# sound.net
KiCad netlist of a schematic drawn in EAGLE
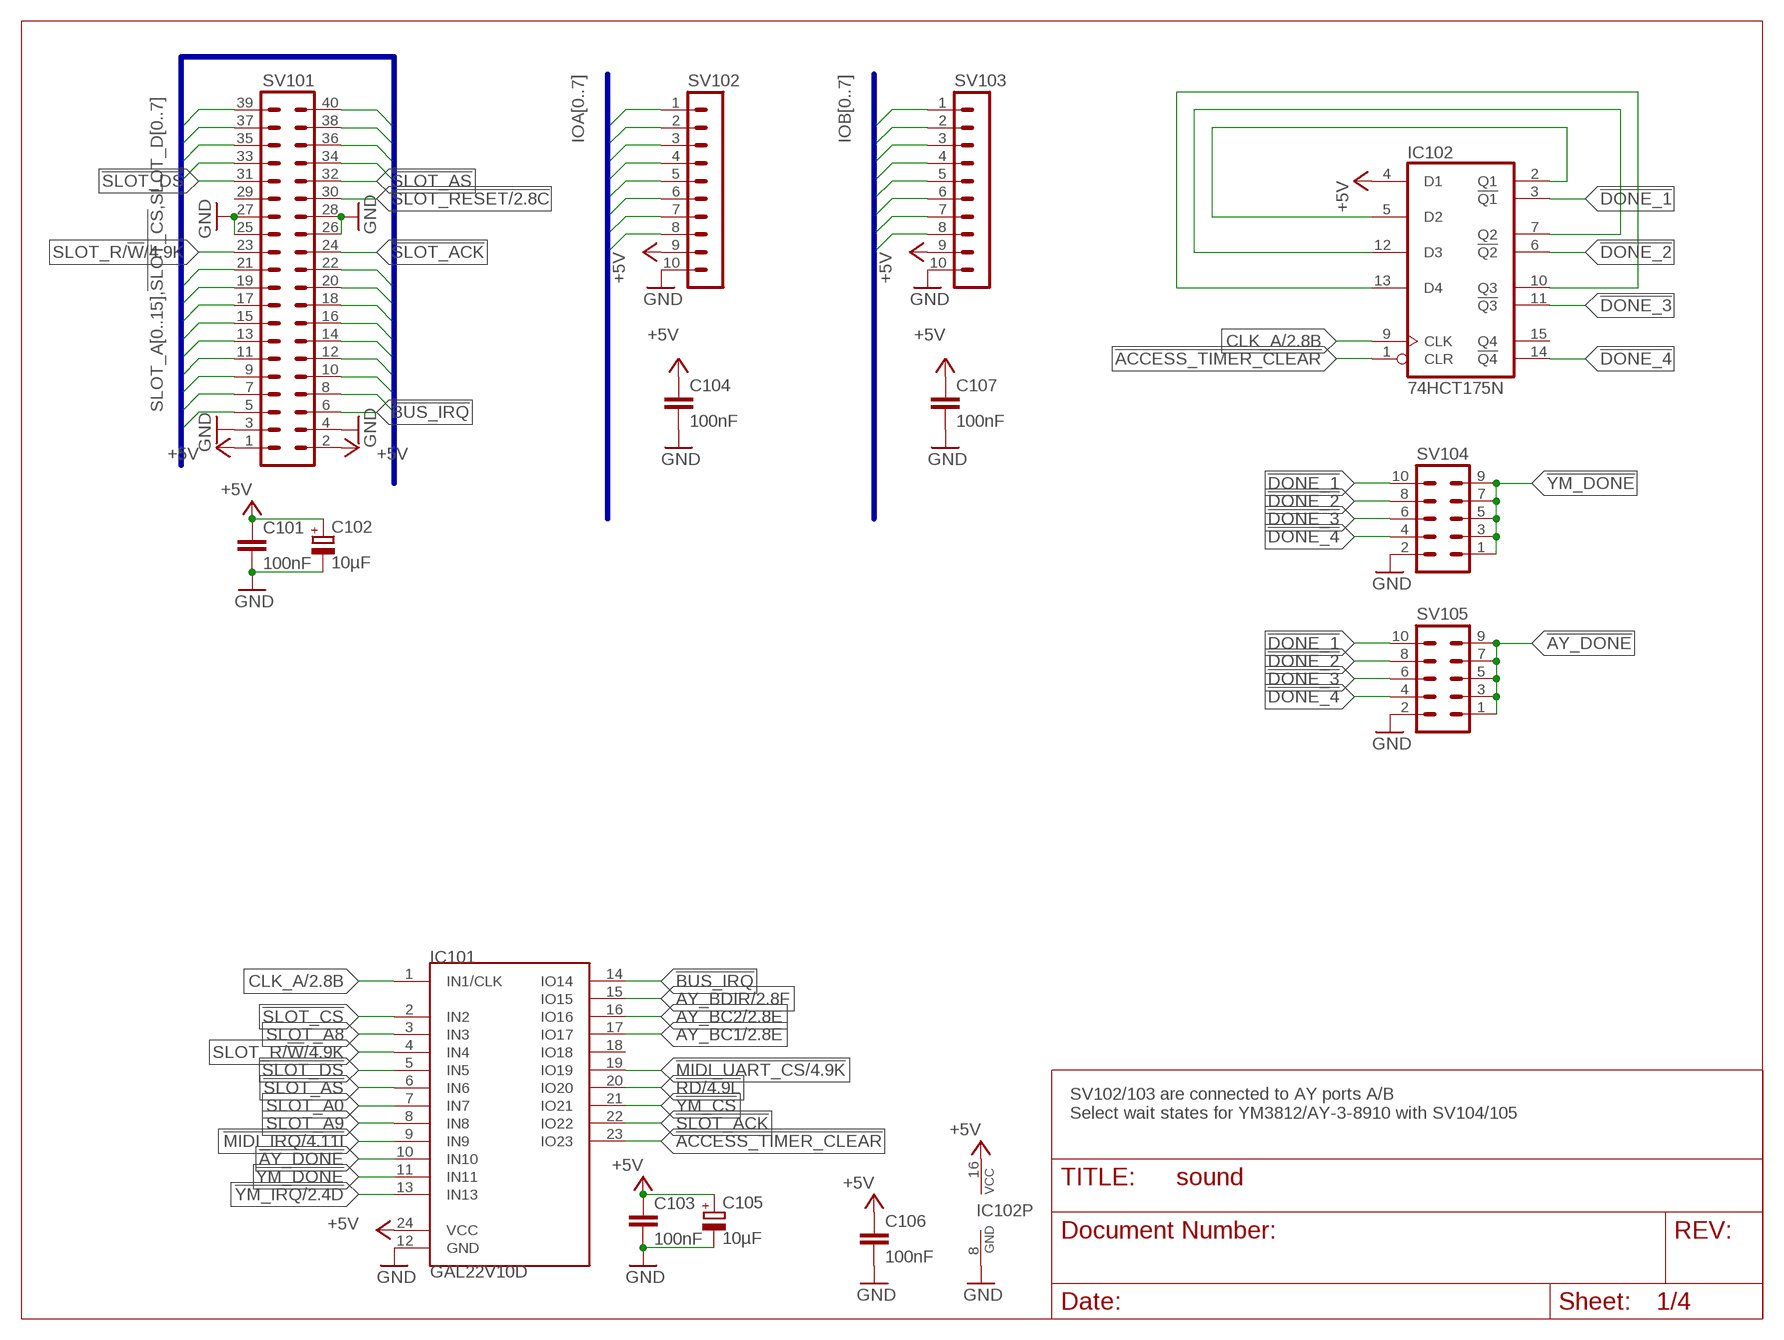
[diagram p0: schematic, sheet 1]
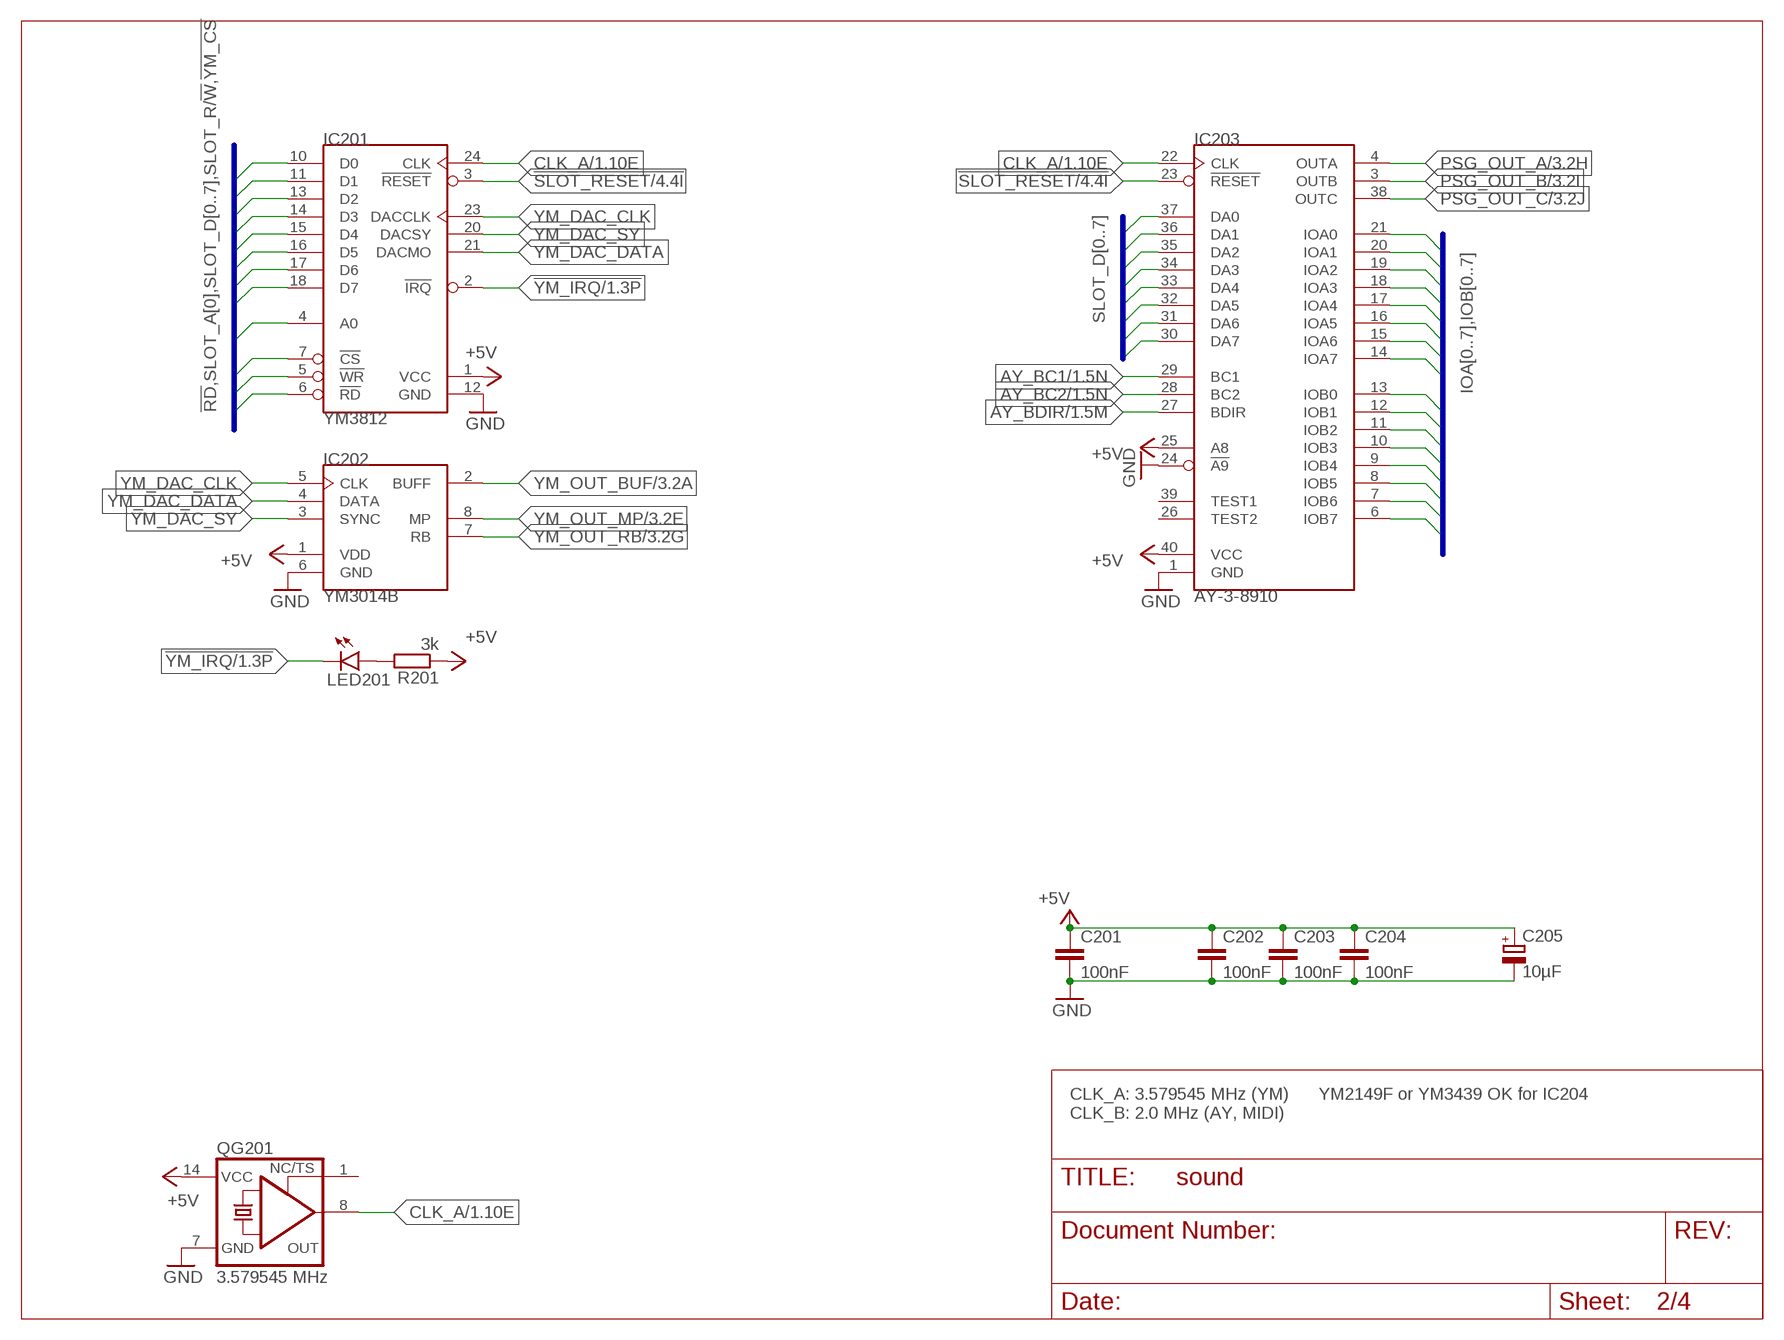
[diagram p1: schematic, sheet 2]
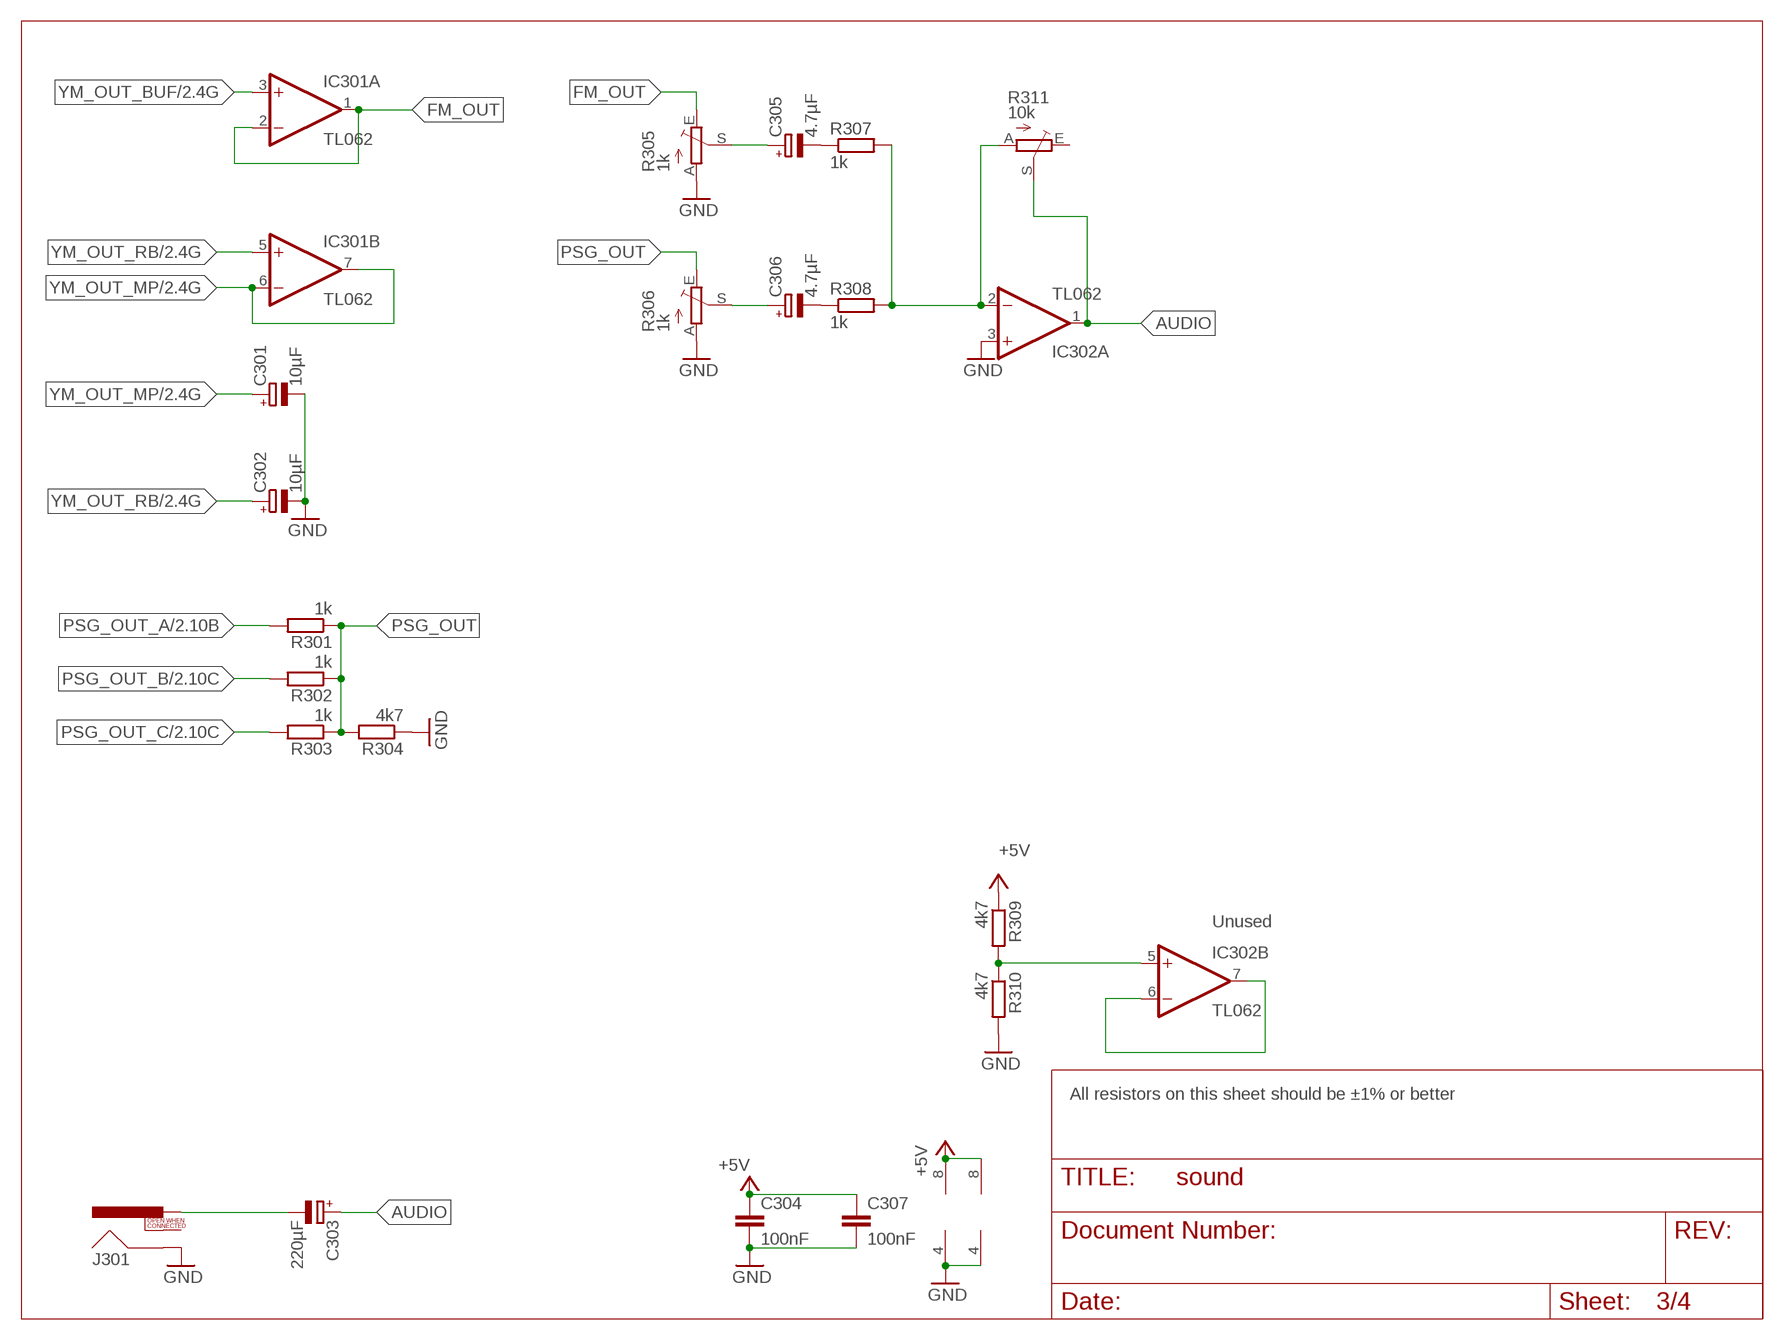
[diagram p2: schematic, sheet 3]
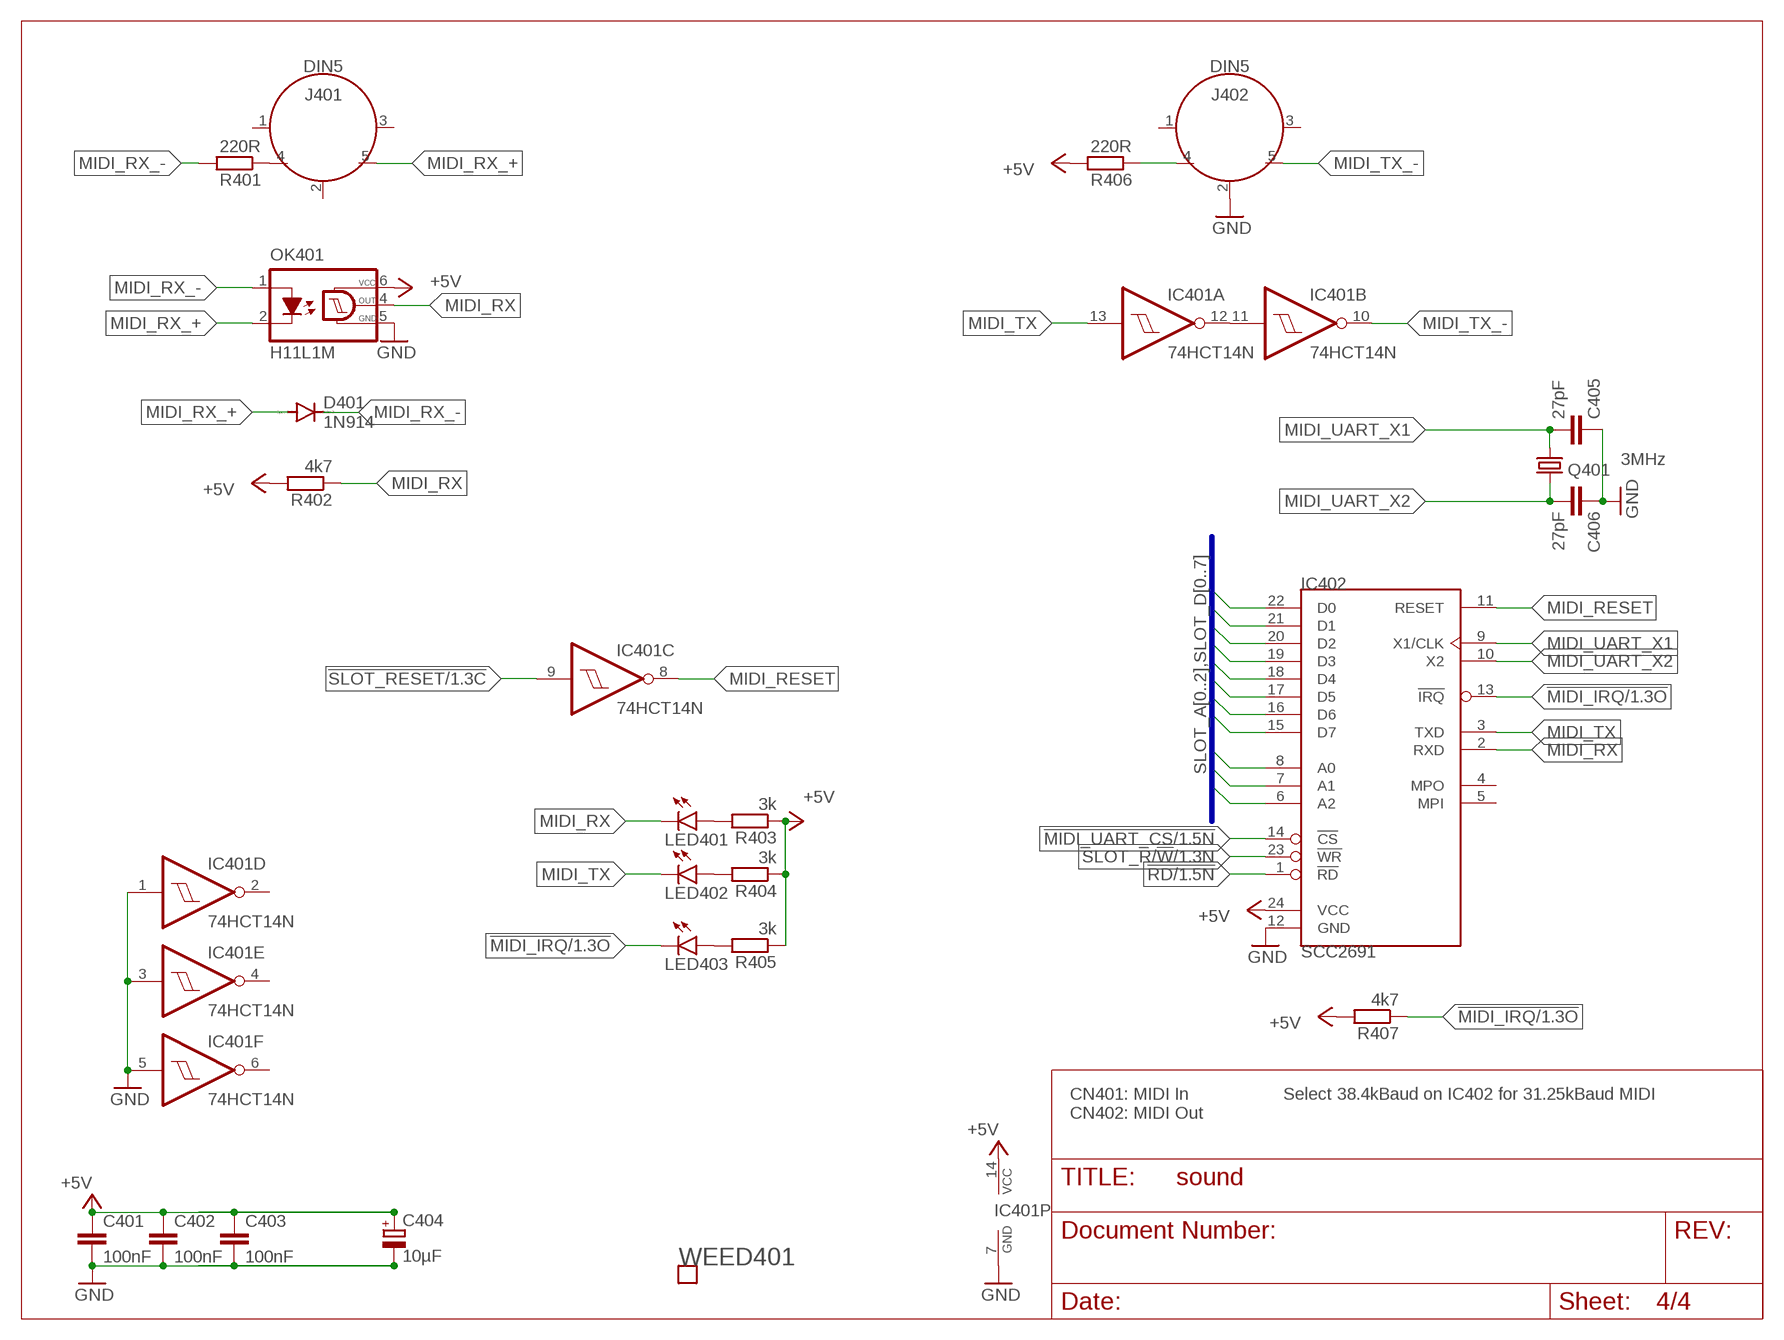
[diagram p3: schematic, sheet 4]

(export (version "E")
  (design (tool "Eeschema 10.0.6"))
  (components
    (comp (ref "C401")
      (value "100nF")
      (footprint "eagle-import:C0805")
      (libsource (lib "eagle-import") (part "C-EUC0805"))
    )
    (comp (ref "C402")
      (value "100nF")
      (footprint "eagle-import:C0805")
      (libsource (lib "eagle-import") (part "C-EUC0805"))
    )
    (comp (ref "C403")
      (value "100nF")
      (footprint "eagle-import:C0805")
      (libsource (lib "eagle-import") (part "C-EUC0805"))
    )
    (comp (ref "C404")
      (value "10µF")
      (footprint "eagle-import:SMC_B")
      (libsource (lib "eagle-import") (part "CPOL-EUSMCB"))
    )
    (comp (ref "C405")
      (value "27pF")
      (footprint "eagle-import:C0805")
      (libsource (lib "eagle-import") (part "C-EUC0805"))
    )
    (comp (ref "C406")
      (value "27pF")
      (footprint "eagle-import:C0805")
      (libsource (lib "eagle-import") (part "C-EUC0805"))
    )
    (comp (ref "D401")
      (value "1N914")
      (footprint "eagle-import:DO35-10")
      (libsource (lib "eagle-import") (part "1N4148DO35-10"))
    )
    (comp (ref "IC401")
      (value "74HCT14N")
      (footprint "eagle-import:DIL14")
      (fields (field (name "MOUSER") "595-SN74HCT14N") (field (name "MOUSER_SOCKET") "575-1104731441001000"))
      (libsource (lib "eagle-import") (part "7414NHCT"))
    )
    (comp (ref "IC402")
      (value "SCC2691")
      (footprint "eagle-import:DIL24S")
      (libsource (lib "eagle-import") (part "SCC2691"))
    )
    (comp (ref "J401")
      (value "DIN5")
      (footprint "eagle-import:DIN5-RA-PTH")
      (libsource (lib "eagle-import") (part "DIN5"))
    )
    (comp (ref "J402")
      (value "DIN5")
      (footprint "eagle-import:DIN5-RA-PTH")
      (libsource (lib "eagle-import") (part "DIN5"))
    )
    (comp (ref "LED401")
      (value "LEDCHIPLED_1206")
      (footprint "eagle-import:CHIPLED_1206")
      (libsource (lib "eagle-import") (part "LEDCHIPLED_1206"))
    )
    (comp (ref "LED402")
      (value "LEDCHIPLED_1206")
      (footprint "eagle-import:CHIPLED_1206")
      (libsource (lib "eagle-import") (part "LEDCHIPLED_1206"))
    )
    (comp (ref "LED403")
      (value "LEDCHIPLED_1206")
      (footprint "eagle-import:CHIPLED_1206")
      (libsource (lib "eagle-import") (part "LEDCHIPLED_1206"))
    )
    (comp (ref "OK401")
      (value "H11L1M")
      (footprint "eagle-import:DIL06")
      (fields (field (name "MF") "FAIRCHILD SEMICONDUCTOR") (field (name "MPN") "H11L1-M"))
      (libsource (lib "eagle-import") (part "H11LM1"))
    )
    (comp (ref "Q401")
      (value "3MHz")
      (footprint "eagle-import:HC49_S")
      (libsource (lib "eagle-import") (part "CRYSTALHC49S"))
    )
    (comp (ref "R401")
      (value "220R")
      (footprint "eagle-import:R2012")
      (libsource (lib "eagle-import") (part "R-EU_R2012"))
    )
    (comp (ref "R402")
      (value "4k7")
      (footprint "eagle-import:R2012")
      (libsource (lib "eagle-import") (part "R-EU_R2012"))
    )
    (comp (ref "R403")
      (value "3k")
      (footprint "eagle-import:R2012")
      (libsource (lib "eagle-import") (part "R-EU_R2012"))
    )
    (comp (ref "R404")
      (value "3k")
      (footprint "eagle-import:R2012")
      (libsource (lib "eagle-import") (part "R-EU_R2012"))
    )
    (comp (ref "R405")
      (value "3k")
      (footprint "eagle-import:R2012")
      (libsource (lib "eagle-import") (part "R-EU_R2012"))
    )
    (comp (ref "R406")
      (value "220R")
      (footprint "eagle-import:R2012")
      (libsource (lib "eagle-import") (part "R-EU_R2012"))
    )
    (comp (ref "R407")
      (value "4k7")
      (footprint "eagle-import:R2012")
      (libsource (lib "eagle-import") (part "R-EU_R2012"))
    )
    (comp (ref "WEED401")
      (value "WEED")
      (footprint "eagle-import:DOINK")
      (libsource (lib "eagle-import") (part "WEED"))
    )
    (comp (ref "C301")
      (value "10µF")
      (footprint "eagle-import:E2-5")
      (libsource (lib "eagle-import") (part "CPOL-EUE2-5"))
    )
    (comp (ref "C302")
      (value "10µF")
      (footprint "eagle-import:E2-5")
      (libsource (lib "eagle-import") (part "CPOL-EUE2-5"))
    )
    (comp (ref "C303")
      (value "220µF")
      (footprint "eagle-import:E2,5-6")
      (libsource (lib "eagle-import") (part "CPOL-EUE2.5-6"))
    )
    (comp (ref "C304")
      (value "100nF")
      (footprint "eagle-import:C0805")
      (libsource (lib "eagle-import") (part "C-EUC0805"))
    )
    (comp (ref "C305")
      (value "4.7µF")
      (footprint "eagle-import:E2-5")
      (libsource (lib "eagle-import") (part "CPOL-EUE2-5"))
    )
    (comp (ref "C306")
      (value "4.7µF")
      (footprint "eagle-import:E2-5")
      (libsource (lib "eagle-import") (part "CPOL-EUE2-5"))
    )
    (comp (ref "C307")
      (value "100nF")
      (footprint "eagle-import:C0805")
      (libsource (lib "eagle-import") (part "C-EUC0805"))
    )
    (comp (ref "IC301")
      (value "TL062")
      (footprint "eagle-import:DIL08")
      (fields
        (field (name "MOUSER") "595-TL062CP")
        (field (name "MOUSER_SOCKET") "575-1104730841001000")
        (field (name "SPICEPREFIX") "J")
      )
      (libsource (lib "eagle-import") (part "TL062P"))
    )
    (comp (ref "IC302")
      (value "TL062")
      (footprint "eagle-import:DIL08")
      (fields
        (field (name "MOUSER") "595-TL062CP")
        (field (name "MOUSER_SOCKET") "575-1104730841001000")
        (field (name "SPICEPREFIX") "J")
      )
      (libsource (lib "eagle-import") (part "TL062P"))
    )
    (comp (ref "J301")
      (value "RCALOCK")
      (footprint "eagle-import:RCA_LOCK")
      (libsource (lib "eagle-import") (part "RCALOCK"))
    )
    (comp (ref "R301")
      (value "1k")
      (footprint "eagle-import:R2012")
      (libsource (lib "eagle-import") (part "R-EU_R2012"))
    )
    (comp (ref "R302")
      (value "1k")
      (footprint "eagle-import:R2012")
      (libsource (lib "eagle-import") (part "R-EU_R2012"))
    )
    (comp (ref "R303")
      (value "1k")
      (footprint "eagle-import:R2012")
      (libsource (lib "eagle-import") (part "R-EU_R2012"))
    )
    (comp (ref "R304")
      (value "4k7")
      (footprint "eagle-import:R2012")
      (libsource (lib "eagle-import") (part "R-EU_R2012"))
    )
    (comp (ref "R305")
      (value "1k")
      (footprint "eagle-import:PT-10S")
      (fields (field (name "SPICEPREFIX") "J"))
      (libsource (lib "eagle-import") (part "TRIM_EU-PT10S"))
    )
    (comp (ref "R306")
      (value "1k")
      (footprint "eagle-import:PT-10S")
      (fields (field (name "SPICEPREFIX") "J"))
      (libsource (lib "eagle-import") (part "TRIM_EU-PT10S"))
    )
    (comp (ref "R307")
      (value "1k")
      (footprint "eagle-import:R2012")
      (libsource (lib "eagle-import") (part "R-EU_R2012"))
    )
    (comp (ref "R308")
      (value "1k")
      (footprint "eagle-import:R2012")
      (libsource (lib "eagle-import") (part "R-EU_R2012"))
    )
    (comp (ref "R309")
      (value "4k7")
      (footprint "eagle-import:R2012")
      (libsource (lib "eagle-import") (part "R-EU_R2012"))
    )
    (comp (ref "R310")
      (value "4k7")
      (footprint "eagle-import:R2012")
      (libsource (lib "eagle-import") (part "R-EU_R2012"))
    )
    (comp (ref "R311")
      (value "10k")
      (footprint "eagle-import:PT-10S")
      (fields (field (name "SPICEPREFIX") "J"))
      (libsource (lib "eagle-import") (part "TRIM_EU-PT10S"))
    )
    (comp (ref "C101")
      (value "100nF")
      (footprint "eagle-import:C0805")
      (libsource (lib "eagle-import") (part "C-EUC0805"))
    )
    (comp (ref "C102")
      (value "10µF")
      (footprint "eagle-import:SMC_B")
      (libsource (lib "eagle-import") (part "CPOL-EUSMCB"))
    )
    (comp (ref "C103")
      (value "100nF")
      (footprint "eagle-import:C0805")
      (libsource (lib "eagle-import") (part "C-EUC0805"))
    )
    (comp (ref "C104")
      (value "100nF")
      (footprint "eagle-import:C0805")
      (libsource (lib "eagle-import") (part "C-EUC0805"))
    )
    (comp (ref "C105")
      (value "10µF")
      (footprint "eagle-import:SMC_B")
      (libsource (lib "eagle-import") (part "CPOL-EUSMCB"))
    )
    (comp (ref "C106")
      (value "100nF")
      (footprint "eagle-import:C0805")
      (libsource (lib "eagle-import") (part "C-EUC0805"))
    )
    (comp (ref "C107")
      (value "100nF")
      (footprint "eagle-import:C0805")
      (libsource (lib "eagle-import") (part "C-EUC0805"))
    )
    (comp (ref "IC101")
      (value "GAL22V10D")
      (footprint "eagle-import:DIL24S")
      (libsource (lib "eagle-import") (part "GAL22V10DIP24"))
    )
    (comp (ref "IC102")
      (value "74HCT175N")
      (footprint "eagle-import:DIL16")
      (fields (field (name "MOUSER") "595-CD74HCT175E") (field (name "MOUSER_SOCKET") "575-1104731641001000"))
      (libsource (lib "eagle-import") (part "74175NHCT"))
    )
    (comp (ref "SV101")
      (value "MA20-2W")
      (footprint "eagle-import:MA20-2W")
      (libsource (lib "eagle-import") (part "MA20-2W"))
    )
    (comp (ref "SV102")
      (value "MA10-1")
      (footprint "eagle-import:MA10-1")
      (libsource (lib "eagle-import") (part "MA10-1"))
    )
    (comp (ref "SV103")
      (value "MA10-1")
      (footprint "eagle-import:MA10-1")
      (libsource (lib "eagle-import") (part "MA10-1"))
    )
    (comp (ref "SV104")
      (value "MA05-2")
      (footprint "eagle-import:MA05-2")
      (libsource (lib "eagle-import") (part "MA05-2"))
    )
    (comp (ref "SV105")
      (value "MA05-2")
      (footprint "eagle-import:MA05-2")
      (libsource (lib "eagle-import") (part "MA05-2"))
    )
    (comp (ref "C201")
      (value "100nF")
      (footprint "eagle-import:C0805")
      (libsource (lib "eagle-import") (part "C-EUC0805"))
    )
    (comp (ref "C202")
      (value "100nF")
      (footprint "eagle-import:C0805")
      (libsource (lib "eagle-import") (part "C-EUC0805"))
    )
    (comp (ref "C203")
      (value "100nF")
      (footprint "eagle-import:C0805")
      (libsource (lib "eagle-import") (part "C-EUC0805"))
    )
    (comp (ref "C204")
      (value "100nF")
      (footprint "eagle-import:C0805")
      (libsource (lib "eagle-import") (part "C-EUC0805"))
    )
    (comp (ref "C205")
      (value "10µF")
      (footprint "eagle-import:SMC_B")
      (libsource (lib "eagle-import") (part "CPOL-EUSMCB"))
    )
    (comp (ref "IC201")
      (value "YM3812")
      (footprint "eagle-import:DIL24")
      (libsource (lib "eagle-import") (part "YM3812DIL24"))
    )
    (comp (ref "IC202")
      (value "YM3014B")
      (footprint "eagle-import:DIL8")
      (libsource (lib "eagle-import") (part "YM3014BDIL8"))
    )
    (comp (ref "IC203")
      (value "AY-3-8910")
      (footprint "eagle-import:DIL40")
      (libsource (lib "eagle-import") (part "AY-3-8910"))
    )
    (comp (ref "LED201")
      (value "LEDCHIPLED_1206")
      (footprint "eagle-import:CHIPLED_1206")
      (libsource (lib "eagle-import") (part "LEDCHIPLED_1206"))
    )
    (comp (ref "QG201")
      (value "3.579545 MHz")
      (footprint "eagle-import:DIL14S")
      (libsource (lib "eagle-import") (part "XO-14"))
    )
    (comp (ref "R201")
      (value "3k")
      (footprint "eagle-import:R2012")
      (libsource (lib "eagle-import") (part "R-EU_R2012"))
    )
  )
  (nets
    (net (code "2") (name "+5V") (class "Default")
      (node (ref "C101") (pin "1") (pinfunction "1_1") (pintype "passive"))
      (node (ref "C102") (pin "+") (pinfunction "+_+") (pintype "passive"))
      (node (ref "C103") (pin "1") (pinfunction "1_1") (pintype "passive"))
      (node (ref "C104") (pin "1") (pinfunction "1_1") (pintype "passive"))
      (node (ref "C105") (pin "+") (pinfunction "+_+") (pintype "passive"))
      (node (ref "C106") (pin "1") (pinfunction "1_1") (pintype "passive"))
      (node (ref "C107") (pin "1") (pinfunction "1_1") (pintype "passive"))
      (node (ref "C201") (pin "1") (pinfunction "1_1") (pintype "passive"))
      (node (ref "C202") (pin "1") (pinfunction "1_1") (pintype "passive"))
      (node (ref "C203") (pin "1") (pinfunction "1_1") (pintype "passive"))
      (node (ref "C204") (pin "1") (pinfunction "1_1") (pintype "passive"))
      (node (ref "C205") (pin "+") (pinfunction "+_+") (pintype "passive"))
      (node (ref "C304") (pin "1") (pinfunction "1_1") (pintype "passive"))
      (node (ref "C307") (pin "1") (pinfunction "1_1") (pintype "passive"))
      (node (ref "C401") (pin "1") (pinfunction "1_1") (pintype "passive"))
      (node (ref "C402") (pin "1") (pinfunction "1_1") (pintype "passive"))
      (node (ref "C403") (pin "1") (pinfunction "1_1") (pintype "passive"))
      (node (ref "C404") (pin "+") (pinfunction "+_+") (pintype "passive"))
      (node (ref "IC101") (pin "24") (pinfunction "VCC_24") (pintype "power_in"))
      (node (ref "IC102") (pin "16") (pinfunction "VCC_16") (pintype "power_in"))
      (node (ref "IC102") (pin "4") (pinfunction "D1_4") (pintype "input"))
      (node (ref "IC201") (pin "1") (pinfunction "VCC_1") (pintype "power_in"))
      (node (ref "IC202") (pin "1") (pinfunction "VDD_1") (pintype "power_in"))
      (node (ref "IC203") (pin "25") (pinfunction "A8_25") (pintype "input"))
      (node (ref "IC203") (pin "40") (pinfunction "VCC_40") (pintype "power_in"))
      (node (ref "IC301") (pin "8") (pinfunction "V+_8") (pintype "power_in"))
      (node (ref "IC302") (pin "8") (pinfunction "V+_8") (pintype "power_in"))
      (node (ref "IC401") (pin "14") (pinfunction "VCC_14") (pintype "power_in"))
      (node (ref "IC402") (pin "24") (pinfunction "VCC_24") (pintype "power_in"))
      (node (ref "OK401") (pin "6") (pinfunction "VCC_6") (pintype "power_in"))
      (node (ref "QG201") (pin "14") (pinfunction "VCC_14") (pintype "power_in"))
      (node (ref "R201") (pin "1") (pinfunction "1_1") (pintype "passive"))
      (node (ref "R309") (pin "1") (pinfunction "1_1") (pintype "passive"))
      (node (ref "R402") (pin "2") (pinfunction "2_2") (pintype "passive"))
      (node (ref "R403") (pin "1") (pinfunction "1_1") (pintype "passive"))
      (node (ref "R404") (pin "1") (pinfunction "1_1") (pintype "passive"))
      (node (ref "R405") (pin "1") (pinfunction "1_1") (pintype "passive"))
      (node (ref "R406") (pin "2") (pinfunction "2_2") (pintype "passive"))
      (node (ref "R407") (pin "2") (pinfunction "2_2") (pintype "passive"))
      (node (ref "SV101") (pin "1") (pinfunction "1_1") (pintype "passive"))
      (node (ref "SV101") (pin "2") (pinfunction "2_2") (pintype "passive"))
      (node (ref "SV102") (pin "9") (pinfunction "9_9") (pintype "passive"))
      (node (ref "SV103") (pin "9") (pinfunction "9_9") (pintype "passive"))
    )
    (net (code "10") (name "AUDIO") (class "Default")
      (node (ref "C303") (pin "+") (pinfunction "+_+") (pintype "passive"))
      (node (ref "IC302") (pin "1") (pinfunction "OUT_1") (pintype "output"))
      (node (ref "R311") (pin "S") (pinfunction "S_S") (pintype "passive"))
    )
    (net (code "11") (name "AY_BC1") (class "Default")
      (node (ref "IC101") (pin "17") (pinfunction "IO17_17") (pintype "bidirectional"))
      (node (ref "IC203") (pin "29") (pinfunction "BC1_29") (pintype "input"))
    )
    (net (code "12") (name "AY_BC2") (class "Default")
      (node (ref "IC101") (pin "16") (pinfunction "IO16_16") (pintype "bidirectional"))
      (node (ref "IC203") (pin "28") (pinfunction "BC2_28") (pintype "input"))
    )
    (net (code "13") (name "AY_BDIR") (class "Default")
      (node (ref "IC101") (pin "15") (pinfunction "IO15_15") (pintype "bidirectional"))
      (node (ref "IC203") (pin "27") (pinfunction "BDIR_27") (pintype "input"))
    )
    (net (code "14") (name "CLK_A") (class "Default")
      (node (ref "IC101") (pin "1") (pinfunction "IN1/CLK_1") (pintype "input"))
      (node (ref "IC102") (pin "9") (pinfunction "CLK_9") (pintype "input"))
      (node (ref "IC201") (pin "24") (pinfunction "CLK_24") (pintype "input"))
      (node (ref "IC203") (pin "22") (pinfunction "CLK_22") (pintype "input"))
      (node (ref "QG201") (pin "8") (pinfunction "OUT_8") (pintype "output"))
    )
    (net (code "15") (name "FM_OUT") (class "Default")
      (node (ref "IC301") (pin "1") (pinfunction "OUT_1") (pintype "output"))
      (node (ref "IC301") (pin "2") (pinfunction "-IN_2") (pintype "input"))
      (node (ref "R305") (pin "E") (pinfunction "E_E") (pintype "passive"))
    )
    (net (code "16") (name "GND") (class "Default")
      (node (ref "C101") (pin "2") (pinfunction "2_2") (pintype "passive"))
      (node (ref "C102") (pin "-") (pinfunction "-_-") (pintype "passive"))
      (node (ref "C103") (pin "2") (pinfunction "2_2") (pintype "passive"))
      (node (ref "C104") (pin "2") (pinfunction "2_2") (pintype "passive"))
      (node (ref "C105") (pin "-") (pinfunction "-_-") (pintype "passive"))
      (node (ref "C106") (pin "2") (pinfunction "2_2") (pintype "passive"))
      (node (ref "C107") (pin "2") (pinfunction "2_2") (pintype "passive"))
      (node (ref "C201") (pin "2") (pinfunction "2_2") (pintype "passive"))
      (node (ref "C202") (pin "2") (pinfunction "2_2") (pintype "passive"))
      (node (ref "C203") (pin "2") (pinfunction "2_2") (pintype "passive"))
      (node (ref "C204") (pin "2") (pinfunction "2_2") (pintype "passive"))
      (node (ref "C205") (pin "-") (pinfunction "-_-") (pintype "passive"))
      (node (ref "C301") (pin "-") (pinfunction "-_-") (pintype "passive"))
      (node (ref "C302") (pin "-") (pinfunction "-_-") (pintype "passive"))
      (node (ref "C304") (pin "2") (pinfunction "2_2") (pintype "passive"))
      (node (ref "C307") (pin "2") (pinfunction "2_2") (pintype "passive"))
      (node (ref "C401") (pin "2") (pinfunction "2_2") (pintype "passive"))
      (node (ref "C402") (pin "2") (pinfunction "2_2") (pintype "passive"))
      (node (ref "C403") (pin "2") (pinfunction "2_2") (pintype "passive"))
      (node (ref "C404") (pin "-") (pinfunction "-_-") (pintype "passive"))
      (node (ref "C405") (pin "1") (pinfunction "1_1") (pintype "passive"))
      (node (ref "C406") (pin "1") (pinfunction "1_1") (pintype "passive"))
      (node (ref "IC101") (pin "12") (pinfunction "GND_12") (pintype "power_in"))
      (node (ref "IC102") (pin "8") (pinfunction "GND_8") (pintype "power_in"))
      (node (ref "IC201") (pin "12") (pinfunction "GND_12") (pintype "power_in"))
      (node (ref "IC202") (pin "6") (pinfunction "GND_6") (pintype "power_in"))
      (node (ref "IC203") (pin "1") (pinfunction "GND_1") (pintype "power_in"))
      (node (ref "IC203") (pin "24") (pinfunction "~{A9}_24") (pintype "input"))
      (node (ref "IC301") (pin "4") (pinfunction "V-_4") (pintype "power_in"))
      (node (ref "IC302") (pin "3") (pinfunction "+IN_3") (pintype "input"))
      (node (ref "IC302") (pin "4") (pinfunction "V-_4") (pintype "power_in"))
      (node (ref "IC401") (pin "1") (pinfunction "I_1") (pintype "input"))
      (node (ref "IC401") (pin "3") (pinfunction "I_3") (pintype "input"))
      (node (ref "IC401") (pin "5") (pinfunction "I_5") (pintype "input"))
      (node (ref "IC401") (pin "7") (pinfunction "GND_7") (pintype "power_in"))
      (node (ref "IC402") (pin "12") (pinfunction "GND_12") (pintype "power_in"))
      (node (ref "J301") (pin "SHELL") (pinfunction "SHELL_SHELL") (pintype "bidirectional"))
      (node (ref "J402") (pin "2") (pinfunction "2_2") (pintype "bidirectional"))
      (node (ref "OK401") (pin "5") (pinfunction "GND_5") (pintype "power_in"))
      (node (ref "QG201") (pin "7") (pinfunction "GND_7") (pintype "power_in"))
      (node (ref "R304") (pin "1") (pinfunction "1_1") (pintype "passive"))
      (node (ref "R305") (pin "A") (pinfunction "A_A") (pintype "passive"))
      (node (ref "R306") (pin "A") (pinfunction "A_A") (pintype "passive"))
      (node (ref "R310") (pin "2") (pinfunction "2_2") (pintype "passive"))
      (node (ref "SV101") (pin "25") (pinfunction "25_25") (pintype "passive"))
      (node (ref "SV101") (pin "26") (pinfunction "26_26") (pintype "passive"))
      (node (ref "SV101") (pin "27") (pinfunction "27_27") (pintype "passive"))
      (node (ref "SV101") (pin "28") (pinfunction "28_28") (pintype "passive"))
      (node (ref "SV101") (pin "3") (pinfunction "3_3") (pintype "passive"))
      (node (ref "SV101") (pin "4") (pinfunction "4_4") (pintype "passive"))
      (node (ref "SV102") (pin "10") (pinfunction "10_10") (pintype "passive"))
      (node (ref "SV103") (pin "10") (pinfunction "10_10") (pintype "passive"))
      (node (ref "SV104") (pin "2") (pinfunction "2_2") (pintype "passive"))
      (node (ref "SV105") (pin "2") (pinfunction "2_2") (pintype "passive"))
    )
    (net (code "17") (name "IOA0") (class "Default")
      (node (ref "IC203") (pin "21") (pinfunction "IOA0_21") (pintype "bidirectional"))
      (node (ref "SV102") (pin "1") (pinfunction "1_1") (pintype "passive"))
    )
    (net (code "18") (name "IOA1") (class "Default")
      (node (ref "IC203") (pin "20") (pinfunction "IOA1_20") (pintype "bidirectional"))
      (node (ref "SV102") (pin "2") (pinfunction "2_2") (pintype "passive"))
    )
    (net (code "19") (name "IOA2") (class "Default")
      (node (ref "IC203") (pin "19") (pinfunction "IOA2_19") (pintype "bidirectional"))
      (node (ref "SV102") (pin "3") (pinfunction "3_3") (pintype "passive"))
    )
    (net (code "20") (name "IOA3") (class "Default")
      (node (ref "IC203") (pin "18") (pinfunction "IOA3_18") (pintype "bidirectional"))
      (node (ref "SV102") (pin "4") (pinfunction "4_4") (pintype "passive"))
    )
    (net (code "21") (name "IOA4") (class "Default")
      (node (ref "IC203") (pin "17") (pinfunction "IOA4_17") (pintype "bidirectional"))
      (node (ref "SV102") (pin "5") (pinfunction "5_5") (pintype "passive"))
    )
    (net (code "22") (name "IOA5") (class "Default")
      (node (ref "IC203") (pin "16") (pinfunction "IOA5_16") (pintype "bidirectional"))
      (node (ref "SV102") (pin "6") (pinfunction "6_6") (pintype "passive"))
    )
    (net (code "23") (name "IOA6") (class "Default")
      (node (ref "IC203") (pin "15") (pinfunction "IOA6_15") (pintype "bidirectional"))
      (node (ref "SV102") (pin "7") (pinfunction "7_7") (pintype "passive"))
    )
    (net (code "24") (name "IOA7") (class "Default")
      (node (ref "IC203") (pin "14") (pinfunction "IOA7_14") (pintype "bidirectional"))
      (node (ref "SV102") (pin "8") (pinfunction "8_8") (pintype "passive"))
    )
    (net (code "25") (name "IOB0") (class "Default")
      (node (ref "IC203") (pin "13") (pinfunction "IOB0_13") (pintype "bidirectional"))
      (node (ref "SV103") (pin "1") (pinfunction "1_1") (pintype "passive"))
    )
    (net (code "26") (name "IOB1") (class "Default")
      (node (ref "IC203") (pin "12") (pinfunction "IOB1_12") (pintype "bidirectional"))
      (node (ref "SV103") (pin "2") (pinfunction "2_2") (pintype "passive"))
    )
    (net (code "27") (name "IOB2") (class "Default")
      (node (ref "IC203") (pin "11") (pinfunction "IOB2_11") (pintype "bidirectional"))
      (node (ref "SV103") (pin "3") (pinfunction "3_3") (pintype "passive"))
    )
    (net (code "28") (name "IOB3") (class "Default")
      (node (ref "IC203") (pin "10") (pinfunction "IOB3_10") (pintype "bidirectional"))
      (node (ref "SV103") (pin "4") (pinfunction "4_4") (pintype "passive"))
    )
    (net (code "29") (name "IOB4") (class "Default")
      (node (ref "IC203") (pin "9") (pinfunction "IOB4_9") (pintype "bidirectional"))
      (node (ref "SV103") (pin "5") (pinfunction "5_5") (pintype "passive"))
    )
    (net (code "30") (name "IOB5") (class "Default")
      (node (ref "IC203") (pin "8") (pinfunction "IOB5_8") (pintype "bidirectional"))
      (node (ref "SV103") (pin "6") (pinfunction "6_6") (pintype "passive"))
    )
    (net (code "31") (name "IOB6") (class "Default")
      (node (ref "IC203") (pin "7") (pinfunction "IOB6_7") (pintype "bidirectional"))
      (node (ref "SV103") (pin "7") (pinfunction "7_7") (pintype "passive"))
    )
    (net (code "32") (name "IOB7") (class "Default")
      (node (ref "IC203") (pin "6") (pinfunction "IOB7_6") (pintype "bidirectional"))
      (node (ref "SV103") (pin "8") (pinfunction "8_8") (pintype "passive"))
    )
    (net (code "33") (name "MIDI_RESET") (class "Default")
      (node (ref "IC401") (pin "8") (pinfunction "O_8") (pintype "output"))
      (node (ref "IC402") (pin "11") (pinfunction "RESET_11") (pintype "input"))
    )
    (net (code "34") (name "MIDI_RX") (class "Default")
      (node (ref "IC402") (pin "2") (pinfunction "RXD_2") (pintype "input"))
      (node (ref "LED401") (pin "C") (pinfunction "C_C") (pintype "passive"))
      (node (ref "OK401") (pin "4") (pinfunction "OUT_4") (pintype "output"))
      (node (ref "R402") (pin "1") (pinfunction "1_1") (pintype "passive"))
    )
    (net (code "35") (name "MIDI_RX_+") (class "Default")
      (node (ref "D401") (pin "A") (pinfunction "A_A") (pintype "passive"))
      (node (ref "J401") (pin "5") (pinfunction "5_5") (pintype "bidirectional"))
      (node (ref "OK401") (pin "2") (pinfunction "C_2") (pintype "passive"))
    )
    (net (code "36") (name "MIDI_RX_-") (class "Default")
      (node (ref "D401") (pin "C") (pinfunction "C_C") (pintype "passive"))
      (node (ref "OK401") (pin "1") (pinfunction "A_1") (pintype "passive"))
      (node (ref "R401") (pin "2") (pinfunction "2_2") (pintype "passive"))
    )
    (net (code "37") (name "MIDI_TX") (class "Default")
      (node (ref "IC401") (pin "13") (pinfunction "I_13") (pintype "input"))
      (node (ref "IC402") (pin "3") (pinfunction "TXD_3") (pintype "output"))
      (node (ref "LED402") (pin "C") (pinfunction "C_C") (pintype "passive"))
    )
    (net (code "38") (name "MIDI_TX_-") (class "Default")
      (node (ref "IC401") (pin "10") (pinfunction "O_10") (pintype "output"))
      (node (ref "J402") (pin "5") (pinfunction "5_5") (pintype "bidirectional"))
    )
    (net (code "39") (name "MIDI_UART_X1") (class "Default")
      (node (ref "C405") (pin "2") (pinfunction "2_2") (pintype "passive"))
      (node (ref "IC402") (pin "9") (pinfunction "X1/CLK_9") (pintype "passive"))
      (node (ref "Q401") (pin "1") (pinfunction "1_1") (pintype "passive"))
    )
    (net (code "40") (name "MIDI_UART_X2") (class "Default")
      (node (ref "C406") (pin "2") (pinfunction "2_2") (pintype "passive"))
      (node (ref "IC402") (pin "10") (pinfunction "X2_10") (pintype "passive"))
      (node (ref "Q401") (pin "2") (pinfunction "2_2") (pintype "passive"))
    )
    (net (code "41") (name "Net-(C303-Pad-)") (class "Default")
      (node (ref "C303") (pin "-") (pinfunction "-_-") (pintype "passive"))
      (node (ref "J301") (pin "PIN") (pinfunction "PIN_PIN") (pintype "bidirectional"))
    )
    (net (code "42") (name "Net-(C305-Pad+)") (class "Default")
      (node (ref "C305") (pin "+") (pinfunction "+_+") (pintype "passive"))
      (node (ref "R305") (pin "S") (pinfunction "S_S") (pintype "passive"))
    )
    (net (code "43") (name "Net-(C305-Pad-)") (class "Default")
      (node (ref "C305") (pin "-") (pinfunction "-_-") (pintype "passive"))
      (node (ref "R307") (pin "1") (pinfunction "1_1") (pintype "passive"))
    )
    (net (code "44") (name "Net-(C306-Pad+)") (class "Default")
      (node (ref "C306") (pin "+") (pinfunction "+_+") (pintype "passive"))
      (node (ref "R306") (pin "S") (pinfunction "S_S") (pintype "passive"))
    )
    (net (code "45") (name "Net-(C306-Pad-)") (class "Default")
      (node (ref "C306") (pin "-") (pinfunction "-_-") (pintype "passive"))
      (node (ref "R308") (pin "1") (pinfunction "1_1") (pintype "passive"))
    )
    (net (code "46") (name "Net-(IC102A-D2)") (class "Default")
      (node (ref "IC102") (pin "2") (pinfunction "Q1_2") (pintype "output"))
      (node (ref "IC102") (pin "5") (pinfunction "D2_5") (pintype "input"))
    )
    (net (code "47") (name "Net-(IC102A-D3)") (class "Default")
      (node (ref "IC102") (pin "12") (pinfunction "D3_12") (pintype "input"))
      (node (ref "IC102") (pin "7") (pinfunction "Q2_7") (pintype "output"))
    )
    (net (code "48") (name "Net-(IC102A-D4)") (class "Default")
      (node (ref "IC102") (pin "10") (pinfunction "Q3_10") (pintype "output"))
      (node (ref "IC102") (pin "13") (pinfunction "D4_13") (pintype "input"))
    )
    (net (code "49") (name "Net-(IC302A--IN)") (class "Default")
      (node (ref "IC302") (pin "2") (pinfunction "-IN_2") (pintype "input"))
      (node (ref "R307") (pin "2") (pinfunction "2_2") (pintype "passive"))
      (node (ref "R308") (pin "2") (pinfunction "2_2") (pintype "passive"))
      (node (ref "R311") (pin "A") (pinfunction "A_A") (pintype "passive"))
    )
    (net (code "50") (name "Net-(IC302B-+IN)") (class "Default")
      (node (ref "IC302") (pin "5") (pinfunction "+IN_5") (pintype "input"))
      (node (ref "R309") (pin "2") (pinfunction "2_2") (pintype "passive"))
      (node (ref "R310") (pin "1") (pinfunction "1_1") (pintype "passive"))
    )
    (net (code "51") (name "Net-(IC302B--IN)") (class "Default")
      (node (ref "IC302") (pin "6") (pinfunction "-IN_6") (pintype "input"))
      (node (ref "IC302") (pin "7") (pinfunction "OUT_7") (pintype "output"))
    )
    (net (code "52") (name "Net-(IC401A-O)") (class "Default")
      (node (ref "IC401") (pin "11") (pinfunction "I_11") (pintype "input"))
      (node (ref "IC401") (pin "12") (pinfunction "O_12") (pintype "output"))
    )
    (net (code "53") (name "Net-(J401-Pad4)") (class "Default")
      (node (ref "J401") (pin "4") (pinfunction "4_4") (pintype "bidirectional"))
      (node (ref "R401") (pin "1") (pinfunction "1_1") (pintype "passive"))
    )
    (net (code "54") (name "Net-(J402-Pad4)") (class "Default")
      (node (ref "J402") (pin "4") (pinfunction "4_4") (pintype "bidirectional"))
      (node (ref "R406") (pin "1") (pinfunction "1_1") (pintype "passive"))
    )
    (net (code "55") (name "Net-(LED201-PadA)") (class "Default")
      (node (ref "LED201") (pin "A") (pinfunction "A_A") (pintype "passive"))
      (node (ref "R201") (pin "2") (pinfunction "2_2") (pintype "passive"))
    )
    (net (code "56") (name "Net-(LED401-PadA)") (class "Default")
      (node (ref "LED401") (pin "A") (pinfunction "A_A") (pintype "passive"))
      (node (ref "R403") (pin "2") (pinfunction "2_2") (pintype "passive"))
    )
    (net (code "57") (name "Net-(LED402-PadA)") (class "Default")
      (node (ref "LED402") (pin "A") (pinfunction "A_A") (pintype "passive"))
      (node (ref "R404") (pin "2") (pinfunction "2_2") (pintype "passive"))
    )
    (net (code "58") (name "Net-(LED403-PadA)") (class "Default")
      (node (ref "LED403") (pin "A") (pinfunction "A_A") (pintype "passive"))
      (node (ref "R405") (pin "2") (pinfunction "2_2") (pintype "passive"))
    )
    (net (code "59") (name "PSG_OUT") (class "Default")
      (node (ref "R301") (pin "1") (pinfunction "1_1") (pintype "passive"))
      (node (ref "R302") (pin "1") (pinfunction "1_1") (pintype "passive"))
      (node (ref "R303") (pin "1") (pinfunction "1_1") (pintype "passive"))
      (node (ref "R304") (pin "2") (pinfunction "2_2") (pintype "passive"))
      (node (ref "R306") (pin "E") (pinfunction "E_E") (pintype "passive"))
    )
    (net (code "60") (name "PSG_OUT_A") (class "Default")
      (node (ref "IC203") (pin "4") (pinfunction "OUTA_4") (pintype "output"))
      (node (ref "R301") (pin "2") (pinfunction "2_2") (pintype "passive"))
    )
    (net (code "61") (name "PSG_OUT_B") (class "Default")
      (node (ref "IC203") (pin "3") (pinfunction "OUTB_3") (pintype "output"))
      (node (ref "R302") (pin "2") (pinfunction "2_2") (pintype "passive"))
    )
    (net (code "62") (name "PSG_OUT_C") (class "Default")
      (node (ref "IC203") (pin "38") (pinfunction "OUTC_38") (pintype "output"))
      (node (ref "R303") (pin "2") (pinfunction "2_2") (pintype "passive"))
    )
    (net (code "63") (name "SLOT_A0") (class "Default")
      (node (ref "IC101") (pin "7") (pinfunction "IN7_7") (pintype "input"))
      (node (ref "IC201") (pin "4") (pinfunction "A0_4") (pintype "input"))
      (node (ref "IC402") (pin "8") (pinfunction "A0_8") (pintype "input"))
      (node (ref "SV101") (pin "12") (pinfunction "12_12") (pintype "passive"))
    )
    (net (code "64") (name "SLOT_A1") (class "Default")
      (node (ref "IC402") (pin "7") (pinfunction "A1_7") (pintype "input"))
      (node (ref "SV101") (pin "10") (pinfunction "10_10") (pintype "passive"))
    )
    (net (code "65") (name "SLOT_A2") (class "Default")
      (node (ref "IC402") (pin "6") (pinfunction "A2_6") (pintype "input"))
      (node (ref "SV101") (pin "8") (pinfunction "8_8") (pintype "passive"))
    )
    (net (code "66") (name "SLOT_A8") (class "Default")
      (node (ref "IC101") (pin "3") (pinfunction "IN3_3") (pintype "input"))
      (node (ref "SV101") (pin "16") (pinfunction "16_16") (pintype "passive"))
    )
    (net (code "67") (name "SLOT_A9") (class "Default")
      (node (ref "IC101") (pin "8") (pinfunction "IN8_8") (pintype "input"))
      (node (ref "SV101") (pin "15") (pinfunction "15_15") (pintype "passive"))
    )
    (net (code "68") (name "SLOT_D0") (class "Default")
      (node (ref "IC201") (pin "10") (pinfunction "D0_10") (pintype "bidirectional"))
      (node (ref "IC203") (pin "37") (pinfunction "DA0_37") (pintype "bidirectional"))
      (node (ref "IC402") (pin "22") (pinfunction "D0_22") (pintype "bidirectional"))
      (node (ref "SV101") (pin "35") (pinfunction "35_35") (pintype "passive"))
    )
    (net (code "69") (name "SLOT_D1") (class "Default")
      (node (ref "IC201") (pin "11") (pinfunction "D1_11") (pintype "bidirectional"))
      (node (ref "IC203") (pin "36") (pinfunction "DA1_36") (pintype "bidirectional"))
      (node (ref "IC402") (pin "21") (pinfunction "D1_21") (pintype "bidirectional"))
      (node (ref "SV101") (pin "37") (pinfunction "37_37") (pintype "passive"))
    )
    (net (code "70") (name "SLOT_D2") (class "Default")
      (node (ref "IC201") (pin "13") (pinfunction "D2_13") (pintype "bidirectional"))
      (node (ref "IC203") (pin "35") (pinfunction "DA2_35") (pintype "bidirectional"))
      (node (ref "IC402") (pin "20") (pinfunction "D2_20") (pintype "bidirectional"))
      (node (ref "SV101") (pin "39") (pinfunction "39_39") (pintype "passive"))
    )
    (net (code "71") (name "SLOT_D3") (class "Default")
      (node (ref "IC201") (pin "14") (pinfunction "D3_14") (pintype "bidirectional"))
      (node (ref "IC203") (pin "34") (pinfunction "DA3_34") (pintype "bidirectional"))
      (node (ref "IC402") (pin "19") (pinfunction "D3_19") (pintype "bidirectional"))
      (node (ref "SV101") (pin "40") (pinfunction "40_40") (pintype "passive"))
    )
    (net (code "72") (name "SLOT_D4") (class "Default")
      (node (ref "IC201") (pin "15") (pinfunction "D4_15") (pintype "bidirectional"))
      (node (ref "IC203") (pin "33") (pinfunction "DA4_33") (pintype "bidirectional"))
      (node (ref "IC402") (pin "18") (pinfunction "D4_18") (pintype "bidirectional"))
      (node (ref "SV101") (pin "38") (pinfunction "38_38") (pintype "passive"))
    )
    (net (code "73") (name "SLOT_D5") (class "Default")
      (node (ref "IC201") (pin "16") (pinfunction "D5_16") (pintype "bidirectional"))
      (node (ref "IC203") (pin "32") (pinfunction "DA5_32") (pintype "bidirectional"))
      (node (ref "IC402") (pin "17") (pinfunction "D5_17") (pintype "bidirectional"))
      (node (ref "SV101") (pin "36") (pinfunction "36_36") (pintype "passive"))
    )
    (net (code "74") (name "SLOT_D6") (class "Default")
      (node (ref "IC201") (pin "17") (pinfunction "D6_17") (pintype "bidirectional"))
      (node (ref "IC203") (pin "31") (pinfunction "DA6_31") (pintype "bidirectional"))
      (node (ref "IC402") (pin "16") (pinfunction "D6_16") (pintype "bidirectional"))
      (node (ref "SV101") (pin "34") (pinfunction "34_34") (pintype "passive"))
    )
    (net (code "75") (name "SLOT_D7") (class "Default")
      (node (ref "IC201") (pin "18") (pinfunction "D7_18") (pintype "bidirectional"))
      (node (ref "IC203") (pin "30") (pinfunction "DA7_30") (pintype "bidirectional"))
      (node (ref "IC402") (pin "15") (pinfunction "D7_15") (pintype "bidirectional"))
      (node (ref "SV101") (pin "33") (pinfunction "33_33") (pintype "passive"))
    )
    (net (code "76") (name "SLOT_R{slash}~{W}") (class "Default")
      (node (ref "IC101") (pin "4") (pinfunction "IN4_4") (pintype "input"))
      (node (ref "IC201") (pin "5") (pinfunction "~{WR}_5") (pintype "input"))
      (node (ref "IC402") (pin "23") (pinfunction "~{WR}_23") (pintype "input"))
      (node (ref "SV101") (pin "23") (pinfunction "23_23") (pintype "passive"))
    )
    (net (code "77") (name "YM_DAC_CLK") (class "Default")
      (node (ref "IC201") (pin "23") (pinfunction "DACCLK_23") (pintype "output"))
      (node (ref "IC202") (pin "5") (pinfunction "CLK_5") (pintype "input"))
    )
    (net (code "78") (name "YM_DAC_DATA") (class "Default")
      (node (ref "IC201") (pin "21") (pinfunction "DACMO_21") (pintype "output"))
      (node (ref "IC202") (pin "4") (pinfunction "DATA_4") (pintype "input"))
    )
    (net (code "79") (name "YM_DAC_SY") (class "Default")
      (node (ref "IC201") (pin "20") (pinfunction "DACSY_20") (pintype "output"))
      (node (ref "IC202") (pin "3") (pinfunction "SYNC_3") (pintype "input"))
    )
    (net (code "80") (name "YM_OUT_BUF") (class "Default")
      (node (ref "IC202") (pin "2") (pinfunction "BUFF_2") (pintype "output"))
      (node (ref "IC301") (pin "3") (pinfunction "+IN_3") (pintype "input"))
    )
    (net (code "81") (name "YM_OUT_MP") (class "Default")
      (node (ref "C301") (pin "+") (pinfunction "+_+") (pintype "passive"))
      (node (ref "IC202") (pin "8") (pinfunction "MP_8") (pintype "output"))
      (node (ref "IC301") (pin "6") (pinfunction "-IN_6") (pintype "input"))
      (node (ref "IC301") (pin "7") (pinfunction "OUT_7") (pintype "output"))
    )
    (net (code "82") (name "YM_OUT_RB") (class "Default")
      (node (ref "C302") (pin "+") (pinfunction "+_+") (pintype "passive"))
      (node (ref "IC202") (pin "7") (pinfunction "RB_7") (pintype "output"))
      (node (ref "IC301") (pin "5") (pinfunction "+IN_5") (pintype "input"))
    )
    (net (code "83") (name "unconnected-(IC101-IO18-Pad18)") (class "Default")
      (node (ref "IC101") (pin "18") (pinfunction "IO18_18") (pintype "bidirectional"))
    )
    (net (code "84") (name "unconnected-(IC102A-Q4-Pad15)") (class "Default")
      (node (ref "IC102") (pin "15") (pinfunction "Q4_15") (pintype "output"))
    )
    (net (code "85") (name "unconnected-(IC203-TEST1-Pad39)") (class "Default")
      (node (ref "IC203") (pin "39") (pinfunction "TEST1_39") (pintype "passive"))
    )
    (net (code "86") (name "unconnected-(IC203-TEST2-Pad26)") (class "Default")
      (node (ref "IC203") (pin "26") (pinfunction "TEST2_26") (pintype "passive"))
    )
    (net (code "87") (name "unconnected-(IC401D-O-Pad2)") (class "Default")
      (node (ref "IC401") (pin "2") (pinfunction "O_2") (pintype "output"))
    )
    (net (code "88") (name "unconnected-(IC401E-O-Pad4)") (class "Default")
      (node (ref "IC401") (pin "4") (pinfunction "O_4") (pintype "output"))
    )
    (net (code "89") (name "unconnected-(IC401F-O-Pad6)") (class "Default")
      (node (ref "IC401") (pin "6") (pinfunction "O_6") (pintype "output"))
    )
    (net (code "90") (name "unconnected-(IC402-MPI-Pad5)") (class "Default")
      (node (ref "IC402") (pin "5") (pinfunction "MPI_5") (pintype "input"))
    )
    (net (code "91") (name "unconnected-(IC402-MPO-Pad4)") (class "Default")
      (node (ref "IC402") (pin "4") (pinfunction "MPO_4") (pintype "output"))
    )
    (net (code "92") (name "unconnected-(J301-PadSWITCH)") (class "Default")
      (node (ref "J301") (pin "SWITCH") (pinfunction "SWITCH_SWITCH") (pintype "bidirectional"))
    )
    (net (code "93") (name "unconnected-(J401-Pad1)") (class "Default")
      (node (ref "J401") (pin "1") (pinfunction "1_1") (pintype "bidirectional"))
    )
    (net (code "94") (name "unconnected-(J401-Pad2)") (class "Default")
      (node (ref "J401") (pin "2") (pinfunction "2_2") (pintype "bidirectional"))
    )
    (net (code "95") (name "unconnected-(J401-Pad3)") (class "Default")
      (node (ref "J401") (pin "3") (pinfunction "3_3") (pintype "bidirectional"))
    )
    (net (code "96") (name "unconnected-(J402-Pad1)") (class "Default")
      (node (ref "J402") (pin "1") (pinfunction "1_1") (pintype "bidirectional"))
    )
    (net (code "97") (name "unconnected-(J402-Pad3)") (class "Default")
      (node (ref "J402") (pin "3") (pinfunction "3_3") (pintype "bidirectional"))
    )
    (net (code "98") (name "unconnected-(QG201-TS-Pad1)") (class "Default")
      (node (ref "QG201") (pin "1") (pinfunction "TS_1") (pintype "passive"))
    )
    (net (code "99") (name "unconnected-(R311-PadE)") (class "Default")
      (node (ref "R311") (pin "E") (pinfunction "E_E") (pintype "passive"))
    )
    (net (code "100") (name "unconnected-(SV101-Pad7)") (class "Default")
      (node (ref "SV101") (pin "7") (pinfunction "7_7") (pintype "passive"))
    )
    (net (code "101") (name "unconnected-(SV101-Pad9)") (class "Default")
      (node (ref "SV101") (pin "9") (pinfunction "9_9") (pintype "passive"))
    )
    (net (code "102") (name "unconnected-(SV101-Pad11)") (class "Default")
      (node (ref "SV101") (pin "11") (pinfunction "11_11") (pintype "passive"))
    )
    (net (code "103") (name "unconnected-(SV101-Pad13)") (class "Default")
      (node (ref "SV101") (pin "13") (pinfunction "13_13") (pintype "passive"))
    )
    (net (code "104") (name "unconnected-(SV101-Pad14)") (class "Default")
      (node (ref "SV101") (pin "14") (pinfunction "14_14") (pintype "passive"))
    )
    (net (code "105") (name "unconnected-(SV101-Pad17)") (class "Default")
      (node (ref "SV101") (pin "17") (pinfunction "17_17") (pintype "passive"))
    )
    (net (code "106") (name "unconnected-(SV101-Pad18)") (class "Default")
      (node (ref "SV101") (pin "18") (pinfunction "18_18") (pintype "passive"))
    )
    (net (code "107") (name "unconnected-(SV101-Pad19)") (class "Default")
      (node (ref "SV101") (pin "19") (pinfunction "19_19") (pintype "passive"))
    )
    (net (code "108") (name "unconnected-(SV101-Pad20)") (class "Default")
      (node (ref "SV101") (pin "20") (pinfunction "20_20") (pintype "passive"))
    )
    (net (code "109") (name "unconnected-(SV101-Pad21)") (class "Default")
      (node (ref "SV101") (pin "21") (pinfunction "21_21") (pintype "passive"))
    )
    (net (code "110") (name "unconnected-(SV101-Pad22)") (class "Default")
      (node (ref "SV101") (pin "22") (pinfunction "22_22") (pintype "passive"))
    )
    (net (code "111") (name "unconnected-(SV101-Pad29)") (class "Default")
      (node (ref "SV101") (pin "29") (pinfunction "29_29") (pintype "passive"))
    )
    (net (code "112") (name "~{ACCESS_TIMER_CLEAR}") (class "Default")
      (node (ref "IC101") (pin "23") (pinfunction "IO23_23") (pintype "bidirectional"))
      (node (ref "IC102") (pin "1") (pinfunction "CLR_1") (pintype "input"))
    )
    (net (code "113") (name "~{AY_DONE}") (class "Default")
      (node (ref "IC101") (pin "10") (pinfunction "IN10_10") (pintype "input"))
      (node (ref "SV105") (pin "1") (pinfunction "1_1") (pintype "passive"))
      (node (ref "SV105") (pin "3") (pinfunction "3_3") (pintype "passive"))
      (node (ref "SV105") (pin "5") (pinfunction "5_5") (pintype "passive"))
      (node (ref "SV105") (pin "7") (pinfunction "7_7") (pintype "passive"))
      (node (ref "SV105") (pin "9") (pinfunction "9_9") (pintype "passive"))
    )
    (net (code "114") (name "~{BUS_IRQ}") (class "Default")
      (node (ref "IC101") (pin "14") (pinfunction "IO14_14") (pintype "bidirectional"))
      (node (ref "SV101") (pin "6") (pinfunction "6_6") (pintype "passive"))
    )
    (net (code "115") (name "~{DONE_1}") (class "Default")
      (node (ref "IC102") (pin "3") (pinfunction "~{Q1}_3") (pintype "output"))
      (node (ref "SV104") (pin "10") (pinfunction "10_10") (pintype "passive"))
      (node (ref "SV105") (pin "10") (pinfunction "10_10") (pintype "passive"))
    )
    (net (code "116") (name "~{DONE_2}") (class "Default")
      (node (ref "IC102") (pin "6") (pinfunction "~{Q2}_6") (pintype "output"))
      (node (ref "SV104") (pin "8") (pinfunction "8_8") (pintype "passive"))
      (node (ref "SV105") (pin "8") (pinfunction "8_8") (pintype "passive"))
    )
    (net (code "117") (name "~{DONE_3}") (class "Default")
      (node (ref "IC102") (pin "11") (pinfunction "~{Q3}_11") (pintype "output"))
      (node (ref "SV104") (pin "6") (pinfunction "6_6") (pintype "passive"))
      (node (ref "SV105") (pin "6") (pinfunction "6_6") (pintype "passive"))
    )
    (net (code "118") (name "~{DONE_4}") (class "Default")
      (node (ref "IC102") (pin "14") (pinfunction "~{Q4}_14") (pintype "output"))
      (node (ref "SV104") (pin "4") (pinfunction "4_4") (pintype "passive"))
      (node (ref "SV105") (pin "4") (pinfunction "4_4") (pintype "passive"))
    )
    (net (code "119") (name "~{MIDI_IRQ}") (class "Default")
      (node (ref "IC101") (pin "9") (pinfunction "IN9_9") (pintype "input"))
      (node (ref "IC402") (pin "13") (pinfunction "~{IRQ}_13") (pintype "output"))
      (node (ref "LED403") (pin "C") (pinfunction "C_C") (pintype "passive"))
      (node (ref "R407") (pin "1") (pinfunction "1_1") (pintype "passive"))
    )
    (net (code "120") (name "~{MIDI_UART_CS}") (class "Default")
      (node (ref "IC101") (pin "19") (pinfunction "IO19_19") (pintype "bidirectional"))
      (node (ref "IC402") (pin "14") (pinfunction "~{CS}_14") (pintype "input"))
    )
    (net (code "121") (name "~{RD}") (class "Default")
      (node (ref "IC101") (pin "20") (pinfunction "IO20_20") (pintype "bidirectional"))
      (node (ref "IC201") (pin "6") (pinfunction "~{RD}_6") (pintype "input"))
      (node (ref "IC402") (pin "1") (pinfunction "~{RD}_1") (pintype "input"))
    )
    (net (code "122") (name "~{SLOT_ACK}") (class "Default")
      (node (ref "IC101") (pin "22") (pinfunction "IO22_22") (pintype "bidirectional"))
      (node (ref "SV101") (pin "24") (pinfunction "24_24") (pintype "passive"))
    )
    (net (code "123") (name "~{SLOT_AS}") (class "Default")
      (node (ref "IC101") (pin "6") (pinfunction "IN6_6") (pintype "input"))
      (node (ref "SV101") (pin "32") (pinfunction "32_32") (pintype "passive"))
    )
    (net (code "124") (name "~{SLOT_CS}") (class "Default")
      (node (ref "IC101") (pin "2") (pinfunction "IN2_2") (pintype "input"))
      (node (ref "SV101") (pin "5") (pinfunction "5_5") (pintype "passive"))
    )
    (net (code "125") (name "~{SLOT_DS}") (class "Default")
      (node (ref "IC101") (pin "5") (pinfunction "IN5_5") (pintype "input"))
      (node (ref "SV101") (pin "31") (pinfunction "31_31") (pintype "passive"))
    )
    (net (code "126") (name "~{SLOT_RESET}") (class "Default")
      (node (ref "IC201") (pin "3") (pinfunction "~{RESET}_3") (pintype "input"))
      (node (ref "IC203") (pin "23") (pinfunction "~{RESET}_23") (pintype "input"))
      (node (ref "IC401") (pin "9") (pinfunction "I_9") (pintype "input"))
      (node (ref "SV101") (pin "30") (pinfunction "30_30") (pintype "passive"))
    )
    (net (code "127") (name "~{YM_CS}") (class "Default")
      (node (ref "IC101") (pin "21") (pinfunction "IO21_21") (pintype "bidirectional"))
      (node (ref "IC201") (pin "7") (pinfunction "~{CS}_7") (pintype "input"))
    )
    (net (code "128") (name "~{YM_DONE}") (class "Default")
      (node (ref "IC101") (pin "11") (pinfunction "IN11_11") (pintype "input"))
      (node (ref "SV104") (pin "1") (pinfunction "1_1") (pintype "passive"))
      (node (ref "SV104") (pin "3") (pinfunction "3_3") (pintype "passive"))
      (node (ref "SV104") (pin "5") (pinfunction "5_5") (pintype "passive"))
      (node (ref "SV104") (pin "7") (pinfunction "7_7") (pintype "passive"))
      (node (ref "SV104") (pin "9") (pinfunction "9_9") (pintype "passive"))
    )
    (net (code "129") (name "~{YM_IRQ}") (class "Default")
      (node (ref "IC101") (pin "13") (pinfunction "IN13_13") (pintype "input"))
      (node (ref "IC201") (pin "2") (pinfunction "~{IRQ}_2") (pintype "output"))
      (node (ref "LED201") (pin "C") (pinfunction "C_C") (pintype "passive"))
    )
  )
)
